# DB_Main-X03.net
KiCad netlist of a schematic drawn in Altium Designer
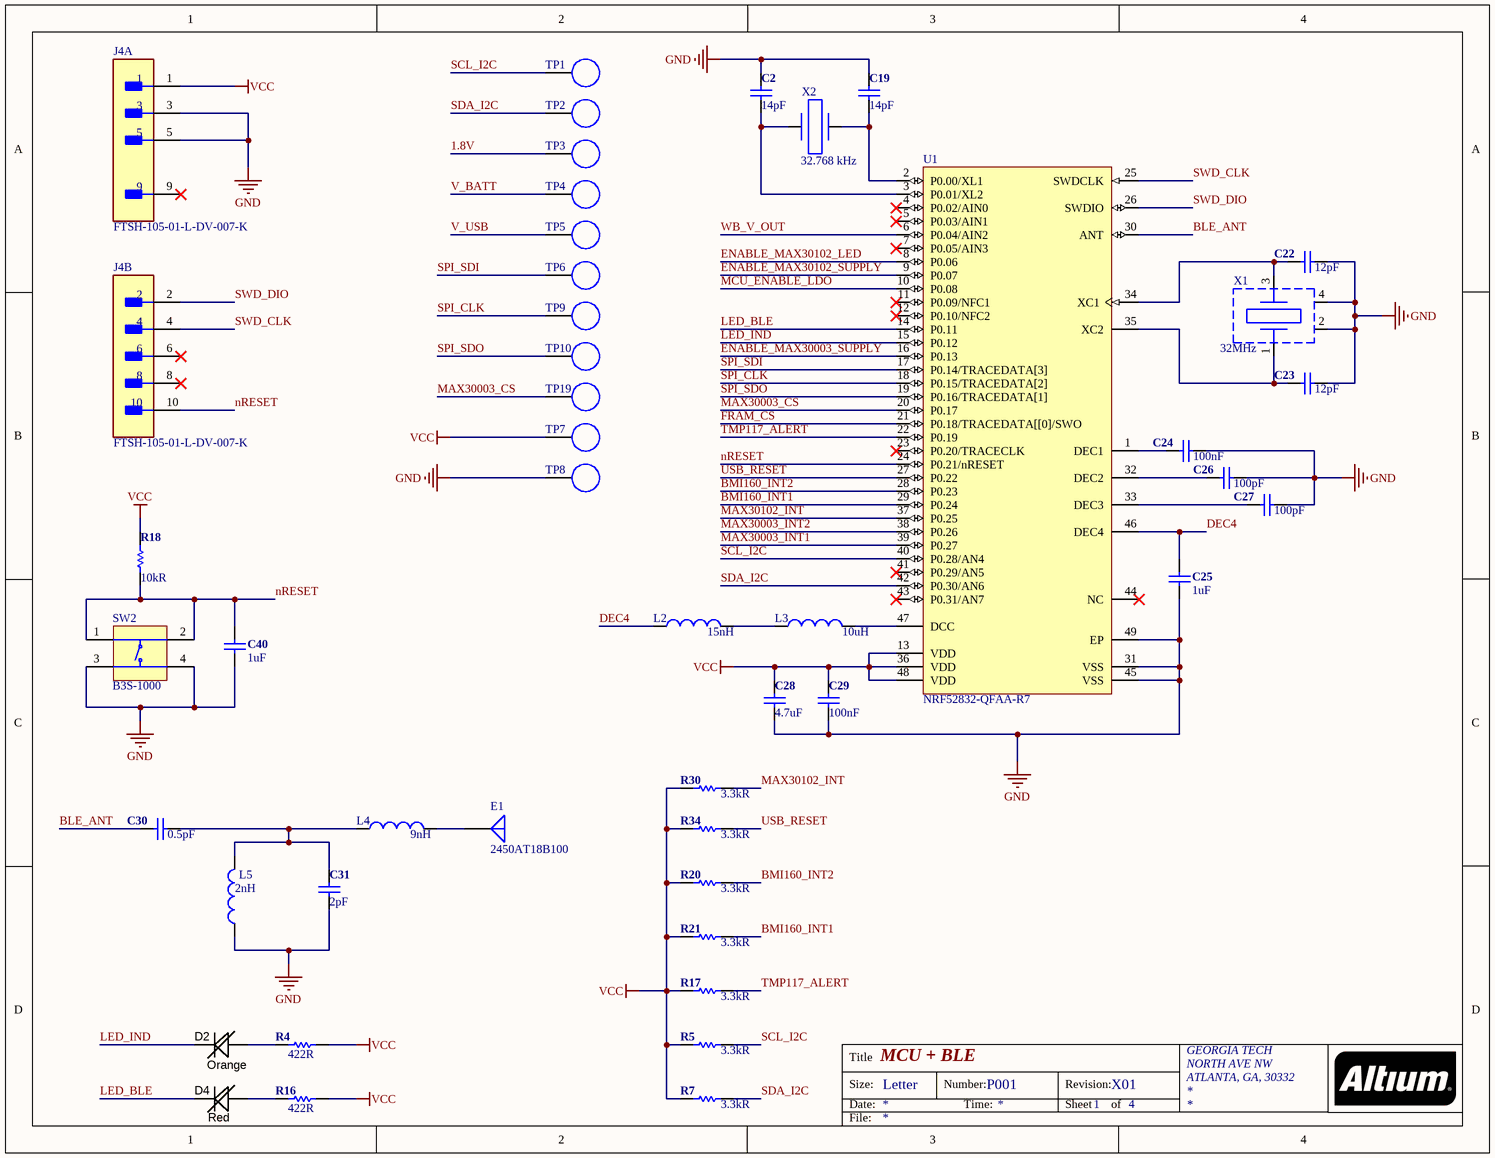
[diagram p0: DB_Main-X03.SchDoc]

(export (version "E")
  (design (tool "Eeschema 10.0.6"))
  (components
    (comp (ref "C2")
      (value "14pF")
      (footprint "C0402")
      (fields
        (field (name "MANUFACTURER") "Kyocera AVX")
        (field (name "MANUFACTURER PART NUMBER") "04025U140FAT2A")
        (field (name "TOLERANCE") "1%")
      )
      (libsource (lib "DB-X01") (part "C-0402(1005)"))
    )
    (comp (ref "C19")
      (value "14pF")
      (footprint "C0402")
      (fields
        (field (name "MANUFACTURER") "Kyocera AVX")
        (field (name "MANUFACTURER PART NUMBER") "04025U140FAT2A")
        (field (name "TOLERANCE") "1%")
      )
      (libsource (lib "DB-X01") (part "C-0402(1005)"))
    )
    (comp (ref "C22")
      (value "12pF")
      (footprint "C0402")
      (fields
        (field (name "MANUFACTURER") "Kyocera AVX")
        (field (name "MANUFACTURER PART NUMBER") "04025U120FAT2A")
        (field (name "TOLERANCE") "1%")
      )
      (libsource (lib "DB-X01") (part "C-0402(1005)"))
    )
    (comp (ref "C23")
      (value "12pF")
      (footprint "C0402")
      (fields
        (field (name "MANUFACTURER") "Kyocera AVX")
        (field (name "MANUFACTURER PART NUMBER") "04025U120FAT2A")
        (field (name "TOLERANCE") "1%")
      )
      (libsource (lib "DB-X01") (part "C-0402(1005)"))
    )
    (comp (ref "C24")
      (value "100nF")
      (footprint "C0402")
      (fields
        (field (name "MANUFACTURER") "Taiyo Yuden")
        (field (name "MANUFACTURER PART NUMBER") "TMK105BJ104KV-F")
        (field (name "TOLERANCE") "10%")
      )
      (libsource (lib "DB-X01") (part "C-0402(1005)"))
    )
    (comp (ref "C25")
      (value "1uF")
      (footprint "C0402")
      (fields
        (field (name "MANUFACTURER") "Yageo")
        (field (name "MANUFACTURER PART NUMBER") "CC0402MRX5R5BB105")
        (field (name "TOLERANCE") "20%")
      )
      (libsource (lib "DB-X01") (part "C-0402(1005)"))
    )
    (comp (ref "C26")
      (value "100pF")
      (footprint "C0402")
      (fields
        (field (name "MANUFACTURER") "Yageo")
        (field (name "MANUFACTURER PART NUMBER") "CC0402FRNPO9BN101")
        (field (name "TOLERANCE") "1%")
      )
      (libsource (lib "DB-X01") (part "C-0402(1005)"))
    )
    (comp (ref "C27")
      (value "100pF")
      (footprint "C0402")
      (fields
        (field (name "MANUFACTURER") "Yageo")
        (field (name "MANUFACTURER PART NUMBER") "CC0402FRNPO9BN101")
        (field (name "TOLERANCE") "1%")
      )
      (libsource (lib "DB-X01") (part "C-0402(1005)"))
    )
    (comp (ref "C28")
      (value "4.7uF")
      (footprint "C0402")
      (description "0402 10 V 4.7 uF ±20% Tolerance X5R Multilayer Ceramic Chip Capacitor")
      (fields
        (field (name "MANUFACTURER") "Murata")
        (field (name "MANUFACTURER PART NUMBER") "GRM155R61A475MEAAD")
      )
      (libsource (lib "DB-X01") (part "C-0402(1005)"))
    )
    (comp (ref "C29")
      (value "100nF")
      (footprint "C0603")
      (fields
        (field (name "MANUFACTURER") "Yageo")
        (field (name "MANUFACTURER PART NUMBER") "CC0402ZRY5V8BB104")
        (field (name "TOLERANCE") "80%")
      )
      (libsource (lib "DB-X01") (part "C-0603(1608)"))
    )
    (comp (ref "C30")
      (value "0.5pF")
      (footprint "C0402")
      (fields
        (field (name "MANUFACTURER") "Murata")
        (field (name "MANUFACTURER PART NUMBER") "GJM1555C1HR50WB01D")
        (field (name "VOLTAGE") "50V")
      )
      (libsource (lib "DB-X01") (part "C-0402(1005)"))
    )
    (comp (ref "C31")
      (value "2pF")
      (footprint "C0402")
      (fields
        (field (name "MANUFACTURER") "Murata")
        (field (name "MANUFACTURER PART NUMBER") "GJM1555C1H2R0BB01D")
      )
      (libsource (lib "DB-X01") (part "C-0402(1005)"))
    )
    (comp (ref "C40")
      (value "1uF")
      (footprint "C0402")
      (fields
        (field (name "MANUFACTURER") "Yageo")
        (field (name "MANUFACTURER PART NUMBER") "CC0402MRX5R5BB105")
        (field (name "TOLERANCE") "20%")
      )
      (libsource (lib "DB-X01") (part "C-0402(1005)"))
    )
    (comp (ref "D2")
      (value "Orange")
      (footprint "LED_0402")
      (description "Single Color LED, Super Bright Orange, Water Clear, 0.8mm")
      (fields
        (field (name "MANUFACTURER") "Kingbright")
        (field (name "MANUFACTURER PART NUMBER") "APHHS1005SECK")
      )
      (libsource (lib "DB-X01") (part "LED_0402(1005)"))
    )
    (comp (ref "D4")
      (value "Red")
      (footprint "LED_0402")
      (description "Single Color LED, Hyper Red, Water Clear, 0.8mm")
      (fields
        (field (name "MANUFACTURER") "Kingbright")
        (field (name "MANUFACTURER PART NUMBER") "APHHS1005SURCK")
      )
      (libsource (lib "DB-X01") (part "LED_0402(1005)"))
    )
    (comp (ref "E1")
      (value "2450AT18B100")
      (footprint "2450AT18B100")
      (description "2.4 GHz BLE Antenna")
      (fields
        (field (name "MANUFACTURER") "Johanson")
        (field (name "MANUFACTURER PART NUMBER") "2450AT18B100E")
      )
      (libsource (lib "DB-X01") (part "2450AT18B100"))
    )
    (comp (ref "J4")
      (value "FTSH-105-01-L-DV-007-K")
      (footprint "FTSH-105-01-L-DV-007-K")
      (description "CONN HEADER SMD 10POS 1.27MM")
      (fields (field (name "MANUFACTURER") "Samtec"))
      (libsource (lib "DB-X01") (part "7c368be3265735b2816d0cab4417f87"))
    )
    (comp (ref "L2")
      (value "15nH")
      (footprint "L0402")
      (description "General Purpose Inductor, 0.015uH, 5%, 1 Element, Ferrite-Core, SMD, 0402")
      (fields
        (field (name "MANUFACTURER") "Taiyo Yuden")
        (field (name "MANUFACTURER PART NUMBER") "HK100515NJ-T")
      )
      (libsource (lib "DB-X01") (part "I-0402(1005)"))
    )
    (comp (ref "L3")
      (value "10uH")
      (footprint "L0603")
      (description "General Purpose Inductor, 10uH, 10%, 1 Element, Ferrite-Core, SMD, 0603")
      (fields
        (field (name "MANUFACTURER") "Taiyo Yuden")
        (field (name "MANUFACTURER PART NUMBER") "CBMF1608T100K")
      )
      (libsource (lib "DB-X01") (part "I-0603(1608)"))
    )
    (comp (ref "L4")
      (value "9nH")
      (footprint "L0402")
      (description "General Purpose Inductor, 0.009uH, 2%, 1 Element, SMD")
      (fields
        (field (name "MANUFACTURER") "Murata")
        (field (name "MANUFACTURER PART NUMBER") "LQW15AN9N0G80D")
      )
      (libsource (lib "DB-X01") (part "I-0402(1005)"))
    )
    (comp (ref "L5")
      (value "2nH")
      (footprint "L0402")
      (description "General Purpose Inductor, 0.002uH, 5%, 1 Element, Ceramic-Core, SMD, 0402")
      (fields
        (field (name "MANUFACTURER") "Abracon")
        (field (name "MANUFACTURER PART NUMBER") "AISC-0402-2N0J-T")
      )
      (libsource (lib "DB-X01") (part "I-0402(1005)"))
    )
    (comp (ref "R4")
      (value "422R")
      (footprint "R0402")
      (description "Fixed Resistor, Thin Film, 0.0625W, 422ohm, 50V, 0.1% +/-Tol, 25ppm/Cel, Surface Mount, 0402")
      (fields
        (field (name "MANUFACTURER") "Yageo")
        (field (name "MANUFACTURER PART NUMBER") "RT0402BRD07422RL")
      )
      (libsource (lib "DB-X01") (part "R-0402(1005)"))
    )
    (comp (ref "R5")
      (value "3.3kR")
      (footprint "R0402")
      (fields
        (field (name "MANUFACTURER") "Yageo")
        (field (name "MANUFACTURER PART NUMBER") "AC0402FR-073K3L")
        (field (name "TOLERANCE") "1%")
      )
      (libsource (lib "DB-X01") (part "R-0402(1005)"))
    )
    (comp (ref "R7")
      (value "3.3kR")
      (footprint "R0402")
      (fields
        (field (name "MANUFACTURER") "Yageo")
        (field (name "MANUFACTURER PART NUMBER") "AC0402FR-073K3L")
        (field (name "TOLERANCE") "1%")
      )
      (libsource (lib "DB-X01") (part "R-0402(1005)"))
    )
    (comp (ref "R16")
      (value "422R")
      (footprint "R0402")
      (description "Fixed Resistor, Thin Film, 0.0625W, 422ohm, 50V, 0.1% +/-Tol, 25ppm/Cel, Surface Mount, 0402")
      (fields
        (field (name "MANUFACTURER") "Yageo")
        (field (name "MANUFACTURER PART NUMBER") "RT0402BRD07422RL")
      )
      (libsource (lib "DB-X01") (part "R-0402(1005)"))
    )
    (comp (ref "R17")
      (value "3.3kR")
      (footprint "R0402")
      (fields
        (field (name "MANUFACTURER") "Yageo")
        (field (name "MANUFACTURER PART NUMBER") "AC0402FR-073K3L")
        (field (name "TOLERANCE") "1%")
      )
      (libsource (lib "DB-X01") (part "R-0402(1005)"))
    )
    (comp (ref "R18")
      (value "10kR")
      (footprint "R0402")
      (fields
        (field (name "MANUFACTURER") "Yageo")
        (field (name "MANUFACTURER PART NUMBER") "AC0402FR-0710KL")
        (field (name "TOLERANCE") "1%")
      )
      (libsource (lib "DB-X01") (part "R-0402(1005)"))
    )
    (comp (ref "R20")
      (value "3.3kR")
      (footprint "R0402")
      (fields
        (field (name "MANUFACTURER") "Yageo")
        (field (name "MANUFACTURER PART NUMBER") "AC0402FR-073K3L")
        (field (name "TOLERANCE") "1%")
      )
      (libsource (lib "DB-X01") (part "R-0402(1005)"))
    )
    (comp (ref "R21")
      (value "3.3kR")
      (footprint "R0402")
      (fields
        (field (name "MANUFACTURER") "Yageo")
        (field (name "MANUFACTURER PART NUMBER") "AC0402FR-073K3L")
        (field (name "TOLERANCE") "1%")
      )
      (libsource (lib "DB-X01") (part "R-0402(1005)"))
    )
    (comp (ref "R30")
      (value "3.3kR")
      (footprint "R0402")
      (fields
        (field (name "MANUFACTURER") "Yageo")
        (field (name "MANUFACTURER PART NUMBER") "AC0402FR-073K3L")
        (field (name "TOLERANCE") "1%")
      )
      (libsource (lib "DB-X01") (part "R-0402(1005)"))
    )
    (comp (ref "R34")
      (value "3.3kR")
      (footprint "R0402")
      (fields
        (field (name "MANUFACTURER") "Yageo")
        (field (name "MANUFACTURER PART NUMBER") "AC0402FR-073K3L")
        (field (name "TOLERANCE") "1%")
      )
      (libsource (lib "DB-X01") (part "R-0402(1005)"))
    )
    (comp (ref "SW2")
      (value "B3S-1000")
      (footprint "OMRON-B3S-1000-4_V")
      (description "Sealed Tactile Switch, SPST-NO, 3 to 24 V, -25 to 70 degC, 4-Pin SMD, RoHS, Bulk")
      (fields (field (name "MANUFACTURER") "Omron") (field (name "MANUFACTURER PART NUMBER") "B3S-1000P"))
      (libsource (lib "Altium Content Vault") (part "SW-SPST-4_A"))
    )
    (comp (ref "TP1")
      (value "S1751-46R")
      (footprint "S1751-46R")
      (description "PC TEST POINT TIN SMD")
      (fields (field (name "MANUFACTURER") "Harwin Inc."))
      (libsource (lib "DB-X01") (part "S1751-46R"))
    )
    (comp (ref "TP2")
      (value "S1751-46R")
      (footprint "S1751-46R")
      (description "PC TEST POINT TIN SMD")
      (fields (field (name "MANUFACTURER") "Harwin Inc."))
      (libsource (lib "DB-X01") (part "S1751-46R"))
    )
    (comp (ref "TP3")
      (value "S1751-46R")
      (footprint "S1751-46R")
      (description "PC TEST POINT TIN SMD")
      (fields (field (name "MANUFACTURER") "Harwin Inc."))
      (libsource (lib "DB-X01") (part "S1751-46R"))
    )
    (comp (ref "TP4")
      (value "S1751-46R")
      (footprint "S1751-46R")
      (description "PC TEST POINT TIN SMD")
      (fields (field (name "MANUFACTURER") "Harwin Inc."))
      (libsource (lib "DB-X01") (part "S1751-46R"))
    )
    (comp (ref "TP5")
      (value "S1751-46R")
      (footprint "S1751-46R")
      (description "PC TEST POINT TIN SMD")
      (fields (field (name "MANUFACTURER") "Harwin Inc."))
      (libsource (lib "DB-X01") (part "S1751-46R"))
    )
    (comp (ref "TP6")
      (value "S1751-46R")
      (footprint "S1751-46R")
      (description "PC TEST POINT TIN SMD")
      (fields (field (name "MANUFACTURER") "Harwin Inc."))
      (libsource (lib "DB-X01") (part "S1751-46R"))
    )
    (comp (ref "TP7")
      (value "S1751-46R")
      (footprint "S1751-46R")
      (description "PC TEST POINT TIN SMD")
      (fields (field (name "MANUFACTURER") "Harwin Inc."))
      (libsource (lib "DB-X01") (part "S1751-46R"))
    )
    (comp (ref "TP8")
      (value "S1751-46R")
      (footprint "S1751-46R")
      (description "PC TEST POINT TIN SMD")
      (fields (field (name "MANUFACTURER") "Harwin Inc."))
      (libsource (lib "DB-X01") (part "S1751-46R"))
    )
    (comp (ref "TP9")
      (value "S1751-46R")
      (footprint "S1751-46R")
      (description "PC TEST POINT TIN SMD")
      (fields (field (name "MANUFACTURER") "Harwin Inc."))
      (libsource (lib "DB-X01") (part "S1751-46R"))
    )
    (comp (ref "TP10")
      (value "S1751-46R")
      (footprint "S1751-46R")
      (description "PC TEST POINT TIN SMD")
      (fields (field (name "MANUFACTURER") "Harwin Inc."))
      (libsource (lib "DB-X01") (part "S1751-46R"))
    )
    (comp (ref "TP19")
      (value "S1751-46R")
      (footprint "S1751-46R")
      (description "PC TEST POINT TIN SMD")
      (fields (field (name "MANUFACTURER") "Harwin Inc."))
      (libsource (lib "DB-X01") (part "S1751-46R"))
    )
    (comp (ref "U1")
      (value "NRF52832-QFAA-R7")
      (footprint "NRF52832-QFAA-R7")
      (fields (field (name "MANUFACTURER") "Nordic Semiconductor"))
      (libsource (lib "DB-X01") (part "NRSC-NRF52832-QF-48"))
    )
    (comp (ref "X1")
      (value "32MHz")
      (footprint "CRYSTAL_1MM6_X_1MM2")
      (description "Parallel - Fundamental Quartz Crystal, 32MHz Nom")
      (fields (field (name "MANUFACTURER") "Diodes") (field (name "MANUFACTURER PART NUMBER") "US3200005Z"))
      (libsource (lib "DB-X01") (part "CRYSTAL_32MHz"))
    )
    (comp (ref "X2")
      (value "32.768 kHz")
      (footprint "CRYSTAL_1MM2_X_1MM0")
      (description "Parallel - Fundamental Quartz Crystal, 0.032768MHz Nom")
      (fields
        (field (name "MANUFACTURER") "ECS International")
        (field (name "MANUFACTURER PART NUMBER") "ECS-.327-9-1210-TR")
      )
      (libsource (lib "DB-X01") (part "CRYSTAL_32K768"))
    )
  )
  (nets
    (net (code "1") (name "/1.8V") (class "Default")
      (node (ref "TP3") (pin "1") (pinfunction "1_1") (pintype "passive"))
    )
    (net (code "2") (name "/BLE_ANT") (class "Default")
      (node (ref "C30") (pin "1") (pinfunction "1_1") (pintype "passive"))
      (node (ref "U1") (pin "30") (pinfunction "ANT_30") (pintype "bidirectional"))
    )
    (net (code "3") (name "/BMI160_INT1") (class "Default")
      (node (ref "R21") (pin "2") (pinfunction "2_2") (pintype "passive"))
      (node (ref "U1") (pin "29") (pinfunction "P0.24_29") (pintype "bidirectional"))
    )
    (net (code "4") (name "/BMI160_INT2") (class "Default")
      (node (ref "R20") (pin "2") (pinfunction "2_2") (pintype "passive"))
      (node (ref "U1") (pin "28") (pinfunction "P0.23_28") (pintype "bidirectional"))
    )
    (net (code "5") (name "/DEC4") (class "Default")
      (node (ref "C25") (pin "2") (pinfunction "2_2") (pintype "passive"))
      (node (ref "L2") (pin "1") (pinfunction "1_1") (pintype "passive"))
      (node (ref "U1") (pin "46") (pinfunction "DEC4_46") (pintype "passive"))
    )
    (net (code "6") (name "/ENABLE_MAX30003_SUPPLY") (class "Default")
      (node (ref "U1") (pin "16") (pinfunction "P0.13_16") (pintype "bidirectional"))
    )
    (net (code "7") (name "/ENABLE_MAX30102_LED") (class "Default")
      (node (ref "U1") (pin "8") (pinfunction "P0.06_8") (pintype "bidirectional"))
    )
    (net (code "8") (name "/ENABLE_MAX30102_SUPPLY") (class "Default")
      (node (ref "U1") (pin "9") (pinfunction "P0.07_9") (pintype "bidirectional"))
    )
    (net (code "9") (name "/FRAM_CS") (class "Default")
      (node (ref "U1") (pin "21") (pinfunction "P0.18/TRACEDATA[[0]/SWO_21") (pintype "bidirectional"))
    )
    (net (code "10") (name "/LED_BLE") (class "Default")
      (node (ref "D4") (pin "K") (pinfunction "K_K") (pintype "passive"))
      (node (ref "U1") (pin "14") (pinfunction "P0.11_14") (pintype "bidirectional"))
    )
    (net (code "11") (name "/LED_IND") (class "Default")
      (node (ref "D2") (pin "K") (pinfunction "K_K") (pintype "passive"))
      (node (ref "U1") (pin "15") (pinfunction "P0.12_15") (pintype "bidirectional"))
    )
    (net (code "12") (name "/MAX30003_CS") (class "Default")
      (node (ref "TP19") (pin "1") (pinfunction "1_1") (pintype "passive"))
      (node (ref "U1") (pin "20") (pinfunction "P0.17_20") (pintype "bidirectional"))
    )
    (net (code "13") (name "/MAX30003_INT1") (class "Default")
      (node (ref "U1") (pin "39") (pinfunction "P0.27_39") (pintype "bidirectional"))
    )
    (net (code "14") (name "/MAX30003_INT2") (class "Default")
      (node (ref "U1") (pin "38") (pinfunction "P0.26_38") (pintype "bidirectional"))
    )
    (net (code "15") (name "/MAX30102_INT") (class "Default")
      (node (ref "R30") (pin "2") (pinfunction "2_2") (pintype "passive"))
      (node (ref "U1") (pin "37") (pinfunction "P0.25_37") (pintype "bidirectional"))
    )
    (net (code "16") (name "/MCU_ENABLE_LDO") (class "Default")
      (node (ref "U1") (pin "10") (pinfunction "P0.08_10") (pintype "bidirectional"))
    )
    (net (code "17") (name "/SCL_I2C") (class "Default")
      (node (ref "R5") (pin "2") (pinfunction "2_2") (pintype "passive"))
      (node (ref "TP1") (pin "1") (pinfunction "1_1") (pintype "passive"))
      (node (ref "U1") (pin "40") (pinfunction "P0.28/AN4_40") (pintype "bidirectional"))
    )
    (net (code "18") (name "/SDA_I2C") (class "Default")
      (node (ref "R7") (pin "2") (pinfunction "2_2") (pintype "passive"))
      (node (ref "TP2") (pin "1") (pinfunction "1_1") (pintype "passive"))
      (node (ref "U1") (pin "42") (pinfunction "P0.30/AN6_42") (pintype "bidirectional"))
    )
    (net (code "19") (name "/SPI_CLK") (class "Default")
      (node (ref "TP9") (pin "1") (pinfunction "1_1") (pintype "passive"))
      (node (ref "U1") (pin "18") (pinfunction "P0.15/TRACEDATA[2]_18") (pintype "bidirectional"))
    )
    (net (code "20") (name "/SPI_SDI") (class "Default")
      (node (ref "TP6") (pin "1") (pinfunction "1_1") (pintype "passive"))
      (node (ref "U1") (pin "17") (pinfunction "P0.14/TRACEDATA[3]_17") (pintype "bidirectional"))
    )
    (net (code "21") (name "/SPI_SDO") (class "Default")
      (node (ref "TP10") (pin "1") (pinfunction "1_1") (pintype "passive"))
      (node (ref "U1") (pin "19") (pinfunction "P0.16/TRACEDATA[1]_19") (pintype "bidirectional"))
    )
    (net (code "22") (name "/SWD_CLK") (class "Default")
      (node (ref "J4") (pin "4") (pinfunction "4_4") (pintype "passive"))
      (node (ref "U1") (pin "25") (pinfunction "SWDCLK_25") (pintype "input"))
    )
    (net (code "23") (name "/SWD_DIO") (class "Default")
      (node (ref "J4") (pin "2") (pinfunction "2_2") (pintype "passive"))
      (node (ref "U1") (pin "26") (pinfunction "SWDIO_26") (pintype "bidirectional"))
    )
    (net (code "24") (name "/TMP117_ALERT") (class "Default")
      (node (ref "R17") (pin "2") (pinfunction "2_2") (pintype "passive"))
      (node (ref "U1") (pin "22") (pinfunction "P0.19_22") (pintype "bidirectional"))
    )
    (net (code "25") (name "/USB_RESET") (class "Default")
      (node (ref "R34") (pin "2") (pinfunction "2_2") (pintype "passive"))
      (node (ref "U1") (pin "27") (pinfunction "P0.22_27") (pintype "bidirectional"))
    )
    (net (code "26") (name "/V_BATT") (class "Default")
      (node (ref "TP4") (pin "1") (pinfunction "1_1") (pintype "passive"))
    )
    (net (code "27") (name "/V_USB") (class "Default")
      (node (ref "TP5") (pin "1") (pinfunction "1_1") (pintype "passive"))
    )
    (net (code "28") (name "/WB_V_OUT") (class "Default")
      (node (ref "U1") (pin "6") (pinfunction "P0.04/AIN2_6") (pintype "bidirectional"))
    )
    (net (code "29") (name "/nRESET") (class "Default")
      (node (ref "C40") (pin "2") (pinfunction "2_2") (pintype "passive"))
      (node (ref "J4") (pin "10") (pinfunction "10_10") (pintype "passive"))
      (node (ref "R18") (pin "2") (pinfunction "2_2") (pintype "passive"))
      (node (ref "SW2") (pin "1") (pinfunction "1_1") (pintype "passive"))
      (node (ref "SW2") (pin "2") (pinfunction "2_2") (pintype "passive"))
      (node (ref "U1") (pin "24") (pinfunction "P0.21/nRESET_24") (pintype "bidirectional"))
    )
    (net (code "30") (name "GND") (class "Default")
      (node (ref "C19") (pin "1") (pinfunction "1_1") (pintype "passive"))
      (node (ref "C2") (pin "1") (pinfunction "1_1") (pintype "passive"))
      (node (ref "C22") (pin "2") (pinfunction "2_2") (pintype "passive"))
      (node (ref "C23") (pin "2") (pinfunction "2_2") (pintype "passive"))
      (node (ref "C24") (pin "2") (pinfunction "2_2") (pintype "passive"))
      (node (ref "C25") (pin "1") (pinfunction "1_1") (pintype "passive"))
      (node (ref "C26") (pin "2") (pinfunction "2_2") (pintype "passive"))
      (node (ref "C27") (pin "2") (pinfunction "2_2") (pintype "passive"))
      (node (ref "C28") (pin "2") (pinfunction "2_2") (pintype "passive"))
      (node (ref "C29") (pin "1") (pinfunction "1_1") (pintype "passive"))
      (node (ref "C31") (pin "2") (pinfunction "2_2") (pintype "passive"))
      (node (ref "C40") (pin "1") (pinfunction "1_1") (pintype "passive"))
      (node (ref "J4") (pin "3") (pinfunction "3_3") (pintype "passive"))
      (node (ref "J4") (pin "5") (pinfunction "5_5") (pintype "passive"))
      (node (ref "L5") (pin "1") (pinfunction "1_1") (pintype "passive"))
      (node (ref "SW2") (pin "3") (pinfunction "3_3") (pintype "passive"))
      (node (ref "SW2") (pin "4") (pinfunction "4_4") (pintype "passive"))
      (node (ref "TP8") (pin "1") (pinfunction "1_1") (pintype "passive"))
      (node (ref "U1") (pin "31") (pinfunction "VSS_31") (pintype "power_in"))
      (node (ref "U1") (pin "45") (pinfunction "VSS_45") (pintype "power_in"))
      (node (ref "U1") (pin "49") (pinfunction "EP_49") (pintype "power_in"))
      (node (ref "X1") (pin "2") (pinfunction "GND_2") (pintype "passive"))
      (node (ref "X1") (pin "4") (pinfunction "GND_4") (pintype "passive"))
    )
    (net (code "31") (name "Net-(C30-Pad2)") (class "Default")
      (node (ref "C30") (pin "2") (pinfunction "2_2") (pintype "passive"))
      (node (ref "C31") (pin "1") (pinfunction "1_1") (pintype "passive"))
      (node (ref "L4") (pin "1") (pinfunction "1_1") (pintype "passive"))
      (node (ref "L5") (pin "2") (pinfunction "2_2") (pintype "passive"))
    )
    (net (code "32") (name "Net-(D2-PadA)") (class "Default")
      (node (ref "D2") (pin "A") (pinfunction "A_A") (pintype "passive"))
      (node (ref "R4") (pin "2") (pinfunction "2_2") (pintype "passive"))
    )
    (net (code "33") (name "Net-(D4-PadA)") (class "Default")
      (node (ref "D4") (pin "A") (pinfunction "A_A") (pintype "passive"))
      (node (ref "R16") (pin "2") (pinfunction "2_2") (pintype "passive"))
    )
    (net (code "34") (name "Net-(E1-A)") (class "Default")
      (node (ref "E1") (pin "1") (pinfunction "A_1") (pintype "passive"))
      (node (ref "L4") (pin "2") (pinfunction "2_2") (pintype "passive"))
    )
    (net (code "35") (name "Net-(L2-Pad2)") (class "Default")
      (node (ref "L2") (pin "2") (pinfunction "2_2") (pintype "passive"))
      (node (ref "L3") (pin "1") (pinfunction "1_1") (pintype "passive"))
    )
    (net (code "36") (name "Net-(U1-DCC)") (class "Default")
      (node (ref "L3") (pin "2") (pinfunction "2_2") (pintype "passive"))
      (node (ref "U1") (pin "47") (pinfunction "DCC_47") (pintype "power_in"))
    )
    (net (code "37") (name "Net-(U1-DEC1)") (class "Default")
      (node (ref "C24") (pin "1") (pinfunction "1_1") (pintype "passive"))
      (node (ref "U1") (pin "1") (pinfunction "DEC1_1") (pintype "passive"))
    )
    (net (code "38") (name "Net-(U1-DEC2)") (class "Default")
      (node (ref "C26") (pin "1") (pinfunction "1_1") (pintype "passive"))
      (node (ref "U1") (pin "32") (pinfunction "DEC2_32") (pintype "passive"))
    )
    (net (code "39") (name "Net-(U1-DEC3)") (class "Default")
      (node (ref "C27") (pin "1") (pinfunction "1_1") (pintype "passive"))
      (node (ref "U1") (pin "33") (pinfunction "DEC3_33") (pintype "passive"))
    )
    (net (code "40") (name "Net-(U1-P0.00{slash}XL1)") (class "Default")
      (node (ref "C19") (pin "2") (pinfunction "2_2") (pintype "passive"))
      (node (ref "U1") (pin "2") (pinfunction "P0.00/XL1_2") (pintype "bidirectional"))
      (node (ref "X2") (pin "2") (pinfunction "2_2") (pintype "passive"))
    )
    (net (code "41") (name "Net-(U1-P0.01{slash}XL2)") (class "Default")
      (node (ref "C2") (pin "2") (pinfunction "2_2") (pintype "passive"))
      (node (ref "U1") (pin "3") (pinfunction "P0.01/XL2_3") (pintype "bidirectional"))
      (node (ref "X2") (pin "1") (pinfunction "1_1") (pintype "passive"))
    )
    (net (code "42") (name "Net-(U1-XC1)") (class "Default")
      (node (ref "C22") (pin "1") (pinfunction "1_1") (pintype "passive"))
      (node (ref "U1") (pin "34") (pinfunction "XC1_34") (pintype "input"))
      (node (ref "X1") (pin "3") (pinfunction "3_3") (pintype "passive"))
    )
    (net (code "43") (name "Net-(U1-XC2)") (class "Default")
      (node (ref "C23") (pin "1") (pinfunction "1_1") (pintype "passive"))
      (node (ref "U1") (pin "35") (pinfunction "XC2_35") (pintype "passive"))
      (node (ref "X1") (pin "1") (pinfunction "1_1") (pintype "passive"))
    )
    (net (code "44") (name "VCC") (class "Default")
      (node (ref "C28") (pin "1") (pinfunction "1_1") (pintype "passive"))
      (node (ref "C29") (pin "2") (pinfunction "2_2") (pintype "passive"))
      (node (ref "J4") (pin "1") (pinfunction "1_1") (pintype "passive"))
      (node (ref "R16") (pin "1") (pinfunction "1_1") (pintype "passive"))
      (node (ref "R17") (pin "1") (pinfunction "1_1") (pintype "passive"))
      (node (ref "R18") (pin "1") (pinfunction "1_1") (pintype "passive"))
      (node (ref "R20") (pin "1") (pinfunction "1_1") (pintype "passive"))
      (node (ref "R21") (pin "1") (pinfunction "1_1") (pintype "passive"))
      (node (ref "R30") (pin "1") (pinfunction "1_1") (pintype "passive"))
      (node (ref "R34") (pin "1") (pinfunction "1_1") (pintype "passive"))
      (node (ref "R4") (pin "1") (pinfunction "1_1") (pintype "passive"))
      (node (ref "R5") (pin "1") (pinfunction "1_1") (pintype "passive"))
      (node (ref "R7") (pin "1") (pinfunction "1_1") (pintype "passive"))
      (node (ref "TP7") (pin "1") (pinfunction "1_1") (pintype "passive"))
      (node (ref "U1") (pin "13") (pinfunction "VDD_13") (pintype "power_in"))
      (node (ref "U1") (pin "36") (pinfunction "VDD_36") (pintype "power_in"))
      (node (ref "U1") (pin "48") (pinfunction "VDD_48") (pintype "power_in"))
    )
    (net (code "45") (name "unconnected-(J4-Pad6)") (class "Default")
      (node (ref "J4") (pin "6") (pinfunction "6_6") (pintype "passive+no_connect"))
    )
    (net (code "46") (name "unconnected-(J4-Pad8)") (class "Default")
      (node (ref "J4") (pin "8") (pinfunction "8_8") (pintype "passive+no_connect"))
    )
    (net (code "47") (name "unconnected-(J4-Pad9)") (class "Default")
      (node (ref "J4") (pin "9") (pinfunction "9_9") (pintype "passive+no_connect"))
    )
    (net (code "48") (name "unconnected-(U1-NC-Pad44)") (class "Default")
      (node (ref "U1") (pin "44") (pinfunction "NC_44") (pintype "passive+no_connect"))
    )
    (net (code "49") (name "unconnected-(U1-P0.02{slash}AIN0-Pad4)") (class "Default")
      (node (ref "U1") (pin "4") (pinfunction "P0.02/AIN0_4") (pintype "bidirectional+no_connect"))
    )
    (net (code "50") (name "unconnected-(U1-P0.03{slash}AIN1-Pad5)") (class "Default")
      (node (ref "U1") (pin "5") (pinfunction "P0.03/AIN1_5") (pintype "bidirectional+no_connect"))
    )
    (net (code "51") (name "unconnected-(U1-P0.05{slash}AIN3-Pad7)") (class "Default")
      (node (ref "U1") (pin "7") (pinfunction "P0.05/AIN3_7") (pintype "bidirectional+no_connect"))
    )
    (net (code "52") (name "unconnected-(U1-P0.09{slash}NFC1-Pad11)") (class "Default")
      (node (ref "U1") (pin "11") (pinfunction "P0.09/NFC1_11") (pintype "bidirectional+no_connect"))
    )
    (net (code "53") (name "unconnected-(U1-P0.10{slash}NFC2-Pad12)") (class "Default")
      (node (ref "U1") (pin "12") (pinfunction "P0.10/NFC2_12") (pintype "bidirectional+no_connect"))
    )
    (net (code "54") (name "unconnected-(U1-P0.20{slash}TRACECLK-Pad23)") (class "Default")
      (node (ref "U1") (pin "23") (pinfunction "P0.20/TRACECLK_23") (pintype "bidirectional+no_connect"))
    )
    (net (code "55") (name "unconnected-(U1-P0.29{slash}AN5-Pad41)") (class "Default")
      (node (ref "U1") (pin "41") (pinfunction "P0.29/AN5_41") (pintype "bidirectional+no_connect"))
    )
    (net (code "56") (name "unconnected-(U1-P0.31{slash}AN7-Pad43)") (class "Default")
      (node (ref "U1") (pin "43") (pinfunction "P0.31/AN7_43") (pintype "bidirectional+no_connect"))
    )
  )
)
